# BK1096_USB.net
KiCad netlist of a schematic drawn in Altium Designer
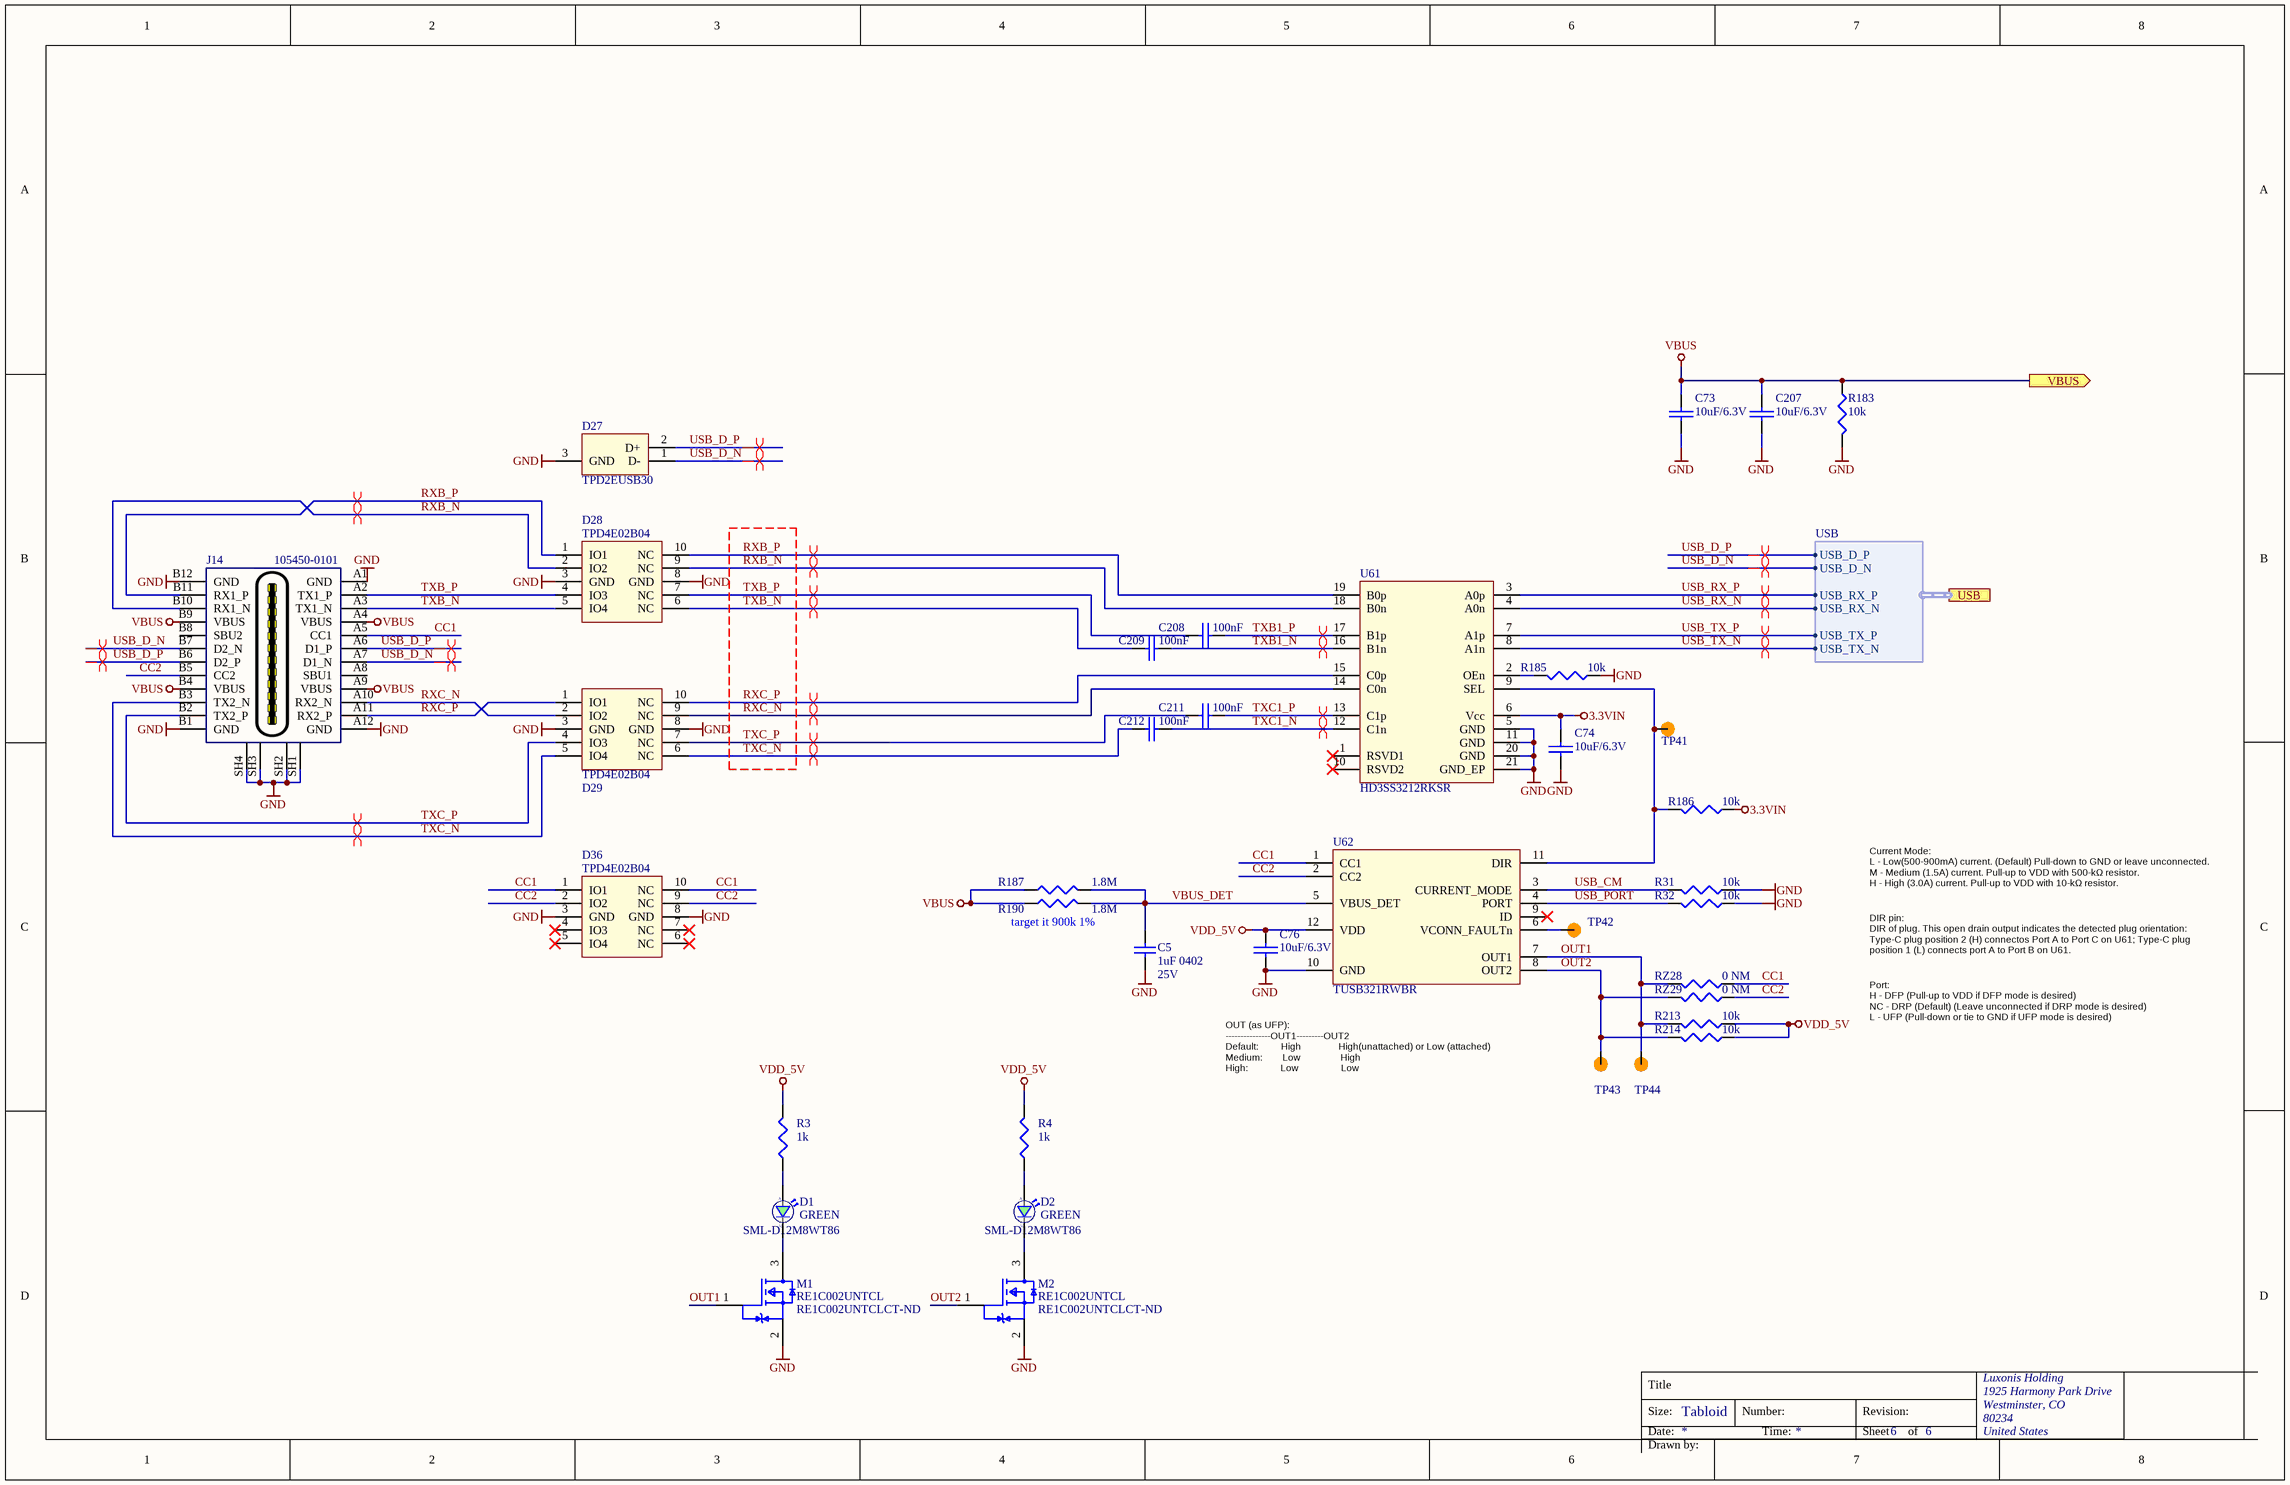
[diagram p0: BK1096_USB.SchDoc]

(export (version "E")
  (design (tool "Eeschema 10.0.6"))
  (components
    (comp (ref "C5")
      (value "1uF 0402")
      (footprint "CAP_Altium_Vault_Generic:CAPC0402(1005)70_N")
      (description "CAP CER 1UF 25V X5R 0402 10%")
      (fields
        (field (name "TOLERANCE") "10%")
        (field (name "VOLTAGE") "25V")
        (field (name "VOLTAGE RATING") "25V")
      )
      (libsource (lib "LuxonisMaster") (part "GRM155R61E105KA12D"))
    )
    (comp (ref "C73")
      (value "10uF/6.3V")
      (footprint "CAPC0402(1005)60_N")
      (description "SMD Multilayer Ceramic Capacitor, 0402 [1005 Metric], 10 µF, 6.3 V, ± 20%, X5R")
      (libsource (lib "*") (part "CAP"))
    )
    (comp (ref "C74")
      (value "10uF/6.3V")
      (footprint "CAPC0402(1005)60_N")
      (description "SMD Multilayer Ceramic Capacitor, 0402 [1005 Metric], 10 µF, 6.3 V, ± 20%, X5R")
      (libsource (lib "*") (part "CAP"))
    )
    (comp (ref "C76")
      (value "10uF/6.3V")
      (footprint "CAPC0402(1005)60_N")
      (description "SMD Multilayer Ceramic Capacitor, 0402 [1005 Metric], 10 µF, 6.3 V, ± 20%, X5R")
      (libsource (lib "*") (part "CAP"))
    )
    (comp (ref "C207")
      (value "10uF/6.3V")
      (footprint "CAPC0402(1005)60_N")
      (description "SMD Multilayer Ceramic Capacitor, 0402 [1005 Metric], 10 µF, 6.3 V, ± 20%, X5R")
      (libsource (lib "*") (part "CAP"))
    )
    (comp (ref "C208")
      (value "100nF")
      (footprint "CAPC0201(0603)33_L")
      (description "SMD Multilayer Ceramic Capacitor, 0201 [0603 Metric], 0.1 µF, 6.3 V, ± 10%, X5R")
      (libsource (lib "MV0235_R1M0E0") (part "CAP"))
    )
    (comp (ref "C209")
      (value "100nF")
      (footprint "CAPC0201(0603)33_L")
      (description "SMD Multilayer Ceramic Capacitor, 0201 [0603 Metric], 0.1 µF, 6.3 V, ± 10%, X5R")
      (libsource (lib "MV0235_R1M0E0") (part "CAP"))
    )
    (comp (ref "C211")
      (value "100nF")
      (footprint "CAPC0201(0603)33_L")
      (description "SMD Multilayer Ceramic Capacitor, 0201 [0603 Metric], 0.1 µF, 6.3 V, ± 10%, X5R")
      (libsource (lib "MV0235_R1M0E0") (part "CAP"))
    )
    (comp (ref "C212")
      (value "100nF")
      (footprint "CAPC0201(0603)33_L")
      (description "SMD Multilayer Ceramic Capacitor, 0201 [0603 Metric], 0.1 µF, 6.3 V, ± 10%, X5R")
      (libsource (lib "MV0235_R1M0E0") (part "CAP"))
    )
    (comp (ref "D1")
      (value "GREEN")
      (footprint "Luxonis:LED_0603")
      (description "LED GREEN DIFFUSED 0603 SMD")
      (fields (field (name "MANUFACTURER") "Rohm") (field (name "MANUFACTURER PART NUMBER") "SML-D12M8WT86"))
      (libsource (lib "Luxonis") (part "LED_GREEN_0603"))
    )
    (comp (ref "D2")
      (value "GREEN")
      (footprint "Luxonis:LED_0603")
      (description "LED GREEN DIFFUSED 0603 SMD")
      (fields (field (name "MANUFACTURER") "Rohm") (field (name "MANUFACTURER PART NUMBER") "SML-D12M8WT86"))
      (libsource (lib "Luxonis") (part "LED_GREEN_0603"))
    )
    (comp (ref "D27")
      (value "TPD2EUSB30")
      (footprint "Luxonis:SOT-3")
      (description "DIODE, ESD, DUAL, USB3.0, SOT-3")
      (libsource (lib "Myriad2") (part "TPD2EUSB30"))
    )
    (comp (ref "D28")
      (value "TPD4E02B04")
      (footprint "Luxonis:DQA-10")
      (description "TVS DIODE 3.6VWM 8.8VC 10USON")
      (libsource (lib "MV0248_R0M0E0") (part "TPD4E02B04"))
    )
    (comp (ref "D29")
      (value "TPD4E02B04")
      (footprint "Luxonis:DQA-10")
      (description "TVS DIODE 3.6VWM 8.8VC 10USON")
      (libsource (lib "MV0248_R0M0E0") (part "TPD4E02B04"))
    )
    (comp (ref "D36")
      (value "TPD4E02B04")
      (footprint "Luxonis:DQA-10")
      (description "TVS DIODE 3.6VWM 8.8VC 10USON")
      (libsource (lib "MV0248_R0M0E0") (part "TPD4E02B04"))
    )
    (comp (ref "J14")
      (value "105450-0101")
      (footprint "Luxonis:Molex_105450-0101")
      (description "USB 3.1 Type C Receptacle SMD RA")
      (libsource (lib "MyriadX_D") (part "Molex_1054500101"))
    )
    (comp (ref "M1")
      (value "RE1C002UNTCL")
      (footprint "Luxonis:SOT-416FL")
      (description "MOSFET N-CH 20V 0.2A EMT3")
      (fields (field (name "SUPPLIER PART NUMBER 1") "RE1C002UNTCLCT-ND"))
      (libsource (lib "Luxonis") (part "RE1C002UNTCL"))
    )
    (comp (ref "M2")
      (value "RE1C002UNTCL")
      (footprint "Luxonis:SOT-416FL")
      (description "MOSFET N-CH 20V 0.2A EMT3")
      (fields (field (name "SUPPLIER PART NUMBER 1") "RE1C002UNTCLCT-ND"))
      (libsource (lib "Luxonis") (part "RE1C002UNTCL"))
    )
    (comp (ref "R3")
      (value "1k")
      (footprint "IPC_RES_CAP:RESC0402(1005)_N")
      (description "SMD Chip Resistor, 1 kohm, 50 V, 0402 [1005 Metric], 62.5 mW, ± 1%")
      (libsource (lib "") (part "RES1_1"))
    )
    (comp (ref "R4")
      (value "1k")
      (footprint "IPC_RES_CAP:RESC0402(1005)_N")
      (description "SMD Chip Resistor, 1 kohm, 50 V, 0402 [1005 Metric], 62.5 mW, ± 1%")
      (libsource (lib "") (part "RES1_1"))
    )
    (comp (ref "R31")
      (value "10k")
      (footprint "RESC0402(1005)_N")
      (description "SMD Chip Resistor, Thick Film, 10 kohm, 50 V, 0402, 100mW, ± 1%")
      (libsource (lib "*") (part "RES1"))
    )
    (comp (ref "R32")
      (value "10k")
      (footprint "RESC0402(1005)_N")
      (description "SMD Chip Resistor, Thick Film, 10 kohm, 50 V, 0402, 100mW, ± 1%")
      (libsource (lib "*") (part "RES1"))
    )
    (comp (ref "R183")
      (value "10k")
      (footprint "RESC0402(1005)_N")
      (description "SMD Chip Resistor, Thick Film, 10 kohm, 50 V, 0402, 100mW, ± 1%")
      (libsource (lib "*") (part "RES1"))
    )
    (comp (ref "R185")
      (value "10k")
      (footprint "RESC0402(1005)_N")
      (description "SMD Chip Resistor, Thick Film, 10 kohm, 50 V, 0402, 100mW, ± 1%")
      (libsource (lib "*") (part "RES1"))
    )
    (comp (ref "R186")
      (value "10k")
      (footprint "RESC0402(1005)_N")
      (description "SMD Chip Resistor, Thick Film, 10 kohm, 50 V, 0402, 100mW, ± 1%")
      (libsource (lib "*") (part "RES1"))
    )
    (comp (ref "R187")
      (value "1.8M")
      (footprint "RESC0402(1005)_N")
      (description "RES SMD 1.8M 1% 0402 50V")
      (libsource (lib "MyriadX_D") (part "R_1.8M_1%_0402"))
    )
    (comp (ref "R190")
      (value "1.8M")
      (footprint "RESC0402(1005)_N")
      (description "RES SMD 1.8M 1% 0402 50V")
      (libsource (lib "MyriadX_D") (part "R_1.8M_1%_0402"))
    )
    (comp (ref "R213")
      (value "10k")
      (footprint "RESC0402(1005)_N")
      (description "SMD Chip Resistor, Thick Film, 10 kohm, 50 V, 0402, 100mW, ± 1%")
      (libsource (lib "*") (part "RES1"))
    )
    (comp (ref "R214")
      (value "10k")
      (footprint "RESC0402(1005)_N")
      (description "SMD Chip Resistor, Thick Film, 10 kohm, 50 V, 0402, 100mW, ± 1%")
      (libsource (lib "*") (part "RES1"))
    )
    (comp (ref "RZ28")
      (value "0 NM")
      (footprint "RESC0603(1608)_N")
      (description "Thick Film Resistors - SMD 0603 Zero Ohms")
      (libsource (lib "*") (part "RES1"))
    )
    (comp (ref "RZ29")
      (value "0 NM")
      (footprint "RESC0603(1608)_N")
      (description "Thick Film Resistors - SMD 0603 Zero Ohms")
      (libsource (lib "*") (part "RES1"))
    )
    (comp (ref "TP41")
      (value "TP_SMD")
      (footprint "TP_0.75MM_SMD_NO-SILK")
      (description "circular pad test point, SMD")
      (libsource (lib "Luxonis") (part "TP_SMD"))
    )
    (comp (ref "TP42")
      (value "TP_SMD")
      (footprint "TP_0.75MM_SMD_NO-SILK")
      (description "circular pad test point, SMD")
      (libsource (lib "Luxonis") (part "TP_SMD"))
    )
    (comp (ref "TP43")
      (value "TP_SMD")
      (footprint "TP_0.75MM_SMD_NO-SILK")
      (description "circular pad test point, SMD")
      (libsource (lib "Luxonis") (part "TP_SMD"))
    )
    (comp (ref "TP44")
      (value "TP_SMD")
      (footprint "TP_0.75MM_SMD_NO-SILK")
      (description "circular pad test point, SMD")
      (libsource (lib "Luxonis") (part "TP_SMD"))
    )
    (comp (ref "U61")
      (value "HD3SS3212RKSR")
      (footprint "Luxonis:VQFN-20")
      (description "Two Channel Differential 2:1/1:2 10Gbps Mux/Demux")
      (libsource (lib "MyriadX_D") (part "HD3SS3212RKSR"))
    )
    (comp (ref "U62")
      (value "TUSB321RWBR")
      (footprint "Luxonis:X2QFN-12")
      (description "USB Type-C  ™ Configuration  Channel  Logic and Port Control  with VCONN")
      (libsource (lib "MyriadX_D") (part "TUSB321RWBR"))
    )
  )
  (nets
    (net (code "2") (name "/CC1") (class "Default")
      (node (ref "D36") (pin "1") (pinfunction "IO1_1") (pintype "passive"))
      (node (ref "D36") (pin "10") (pinfunction "NC_10") (pintype "passive"))
      (node (ref "J14") (pin "A5") (pinfunction "CC1_A5") (pintype "passive"))
      (node (ref "RZ28") (pin "1") (pintype "passive"))
      (node (ref "U62") (pin "1") (pinfunction "CC1_1") (pintype "passive"))
    )
    (net (code "3") (name "/CC2") (class "Default")
      (node (ref "D36") (pin "2") (pinfunction "IO2_2") (pintype "passive"))
      (node (ref "D36") (pin "9") (pinfunction "NC_9") (pintype "passive"))
      (node (ref "J14") (pin "B5") (pinfunction "CC2_B5") (pintype "passive"))
      (node (ref "RZ29") (pin "1") (pintype "passive"))
      (node (ref "U62") (pin "2") (pinfunction "CC2_2") (pintype "passive"))
    )
    (net (code "4") (name "/OUT1") (class "Default")
      (node (ref "M1") (pin "1") (pinfunction "Gate_1") (pintype "passive"))
      (node (ref "R213") (pin "1") (pintype "passive"))
      (node (ref "RZ28") (pin "2") (pintype "passive"))
      (node (ref "TP44") (pin "1") (pintype "passive"))
      (node (ref "U62") (pin "7") (pinfunction "OUT1_7") (pintype "passive"))
    )
    (net (code "5") (name "/OUT2") (class "Default")
      (node (ref "M2") (pin "1") (pinfunction "Gate_1") (pintype "passive"))
      (node (ref "R214") (pin "1") (pintype "passive"))
      (node (ref "RZ29") (pin "2") (pintype "passive"))
      (node (ref "TP43") (pin "1") (pintype "passive"))
      (node (ref "U62") (pin "8") (pinfunction "OUT2_8") (pintype "passive"))
    )
    (net (code "6") (name "/RXB_N") (class "Default")
      (node (ref "D28") (pin "2") (pinfunction "IO2_2") (pintype "passive"))
      (node (ref "D28") (pin "9") (pinfunction "NC_9") (pintype "passive"))
      (node (ref "J14") (pin "B10") (pinfunction "RX1_N_B10") (pintype "passive"))
      (node (ref "U61") (pin "18") (pinfunction "B0n_18") (pintype "passive"))
    )
    (net (code "7") (name "/RXB_P") (class "Default")
      (node (ref "D28") (pin "1") (pinfunction "IO1_1") (pintype "passive"))
      (node (ref "D28") (pin "10") (pinfunction "NC_10") (pintype "passive"))
      (node (ref "J14") (pin "B11") (pinfunction "RX1_P_B11") (pintype "passive"))
      (node (ref "U61") (pin "19") (pinfunction "B0p_19") (pintype "passive"))
    )
    (net (code "8") (name "/RXC_N") (class "Default")
      (node (ref "D29") (pin "2") (pinfunction "IO2_2") (pintype "passive"))
      (node (ref "D29") (pin "9") (pinfunction "NC_9") (pintype "passive"))
      (node (ref "J14") (pin "A10") (pinfunction "RX2_N_A10") (pintype "passive"))
      (node (ref "U61") (pin "14") (pinfunction "C0n_14") (pintype "passive"))
    )
    (net (code "9") (name "/RXC_P") (class "Default")
      (node (ref "D29") (pin "1") (pinfunction "IO1_1") (pintype "passive"))
      (node (ref "D29") (pin "10") (pinfunction "NC_10") (pintype "passive"))
      (node (ref "J14") (pin "A11") (pinfunction "RX2_P_A11") (pintype "passive"))
      (node (ref "U61") (pin "15") (pinfunction "C0p_15") (pintype "passive"))
    )
    (net (code "10") (name "/TXB1_N") (class "Default")
      (node (ref "C209") (pin "1") (pinfunction "1_1") (pintype "passive"))
      (node (ref "U61") (pin "16") (pinfunction "B1n_16") (pintype "passive"))
    )
    (net (code "11") (name "/TXB1_P") (class "Default")
      (node (ref "C208") (pin "1") (pinfunction "1_1") (pintype "passive"))
      (node (ref "U61") (pin "17") (pinfunction "B1p_17") (pintype "passive"))
    )
    (net (code "12") (name "/TXB_N") (class "Default")
      (node (ref "C209") (pin "2") (pinfunction "2_2") (pintype "passive"))
      (node (ref "D28") (pin "5") (pinfunction "IO4_5") (pintype "passive"))
      (node (ref "D28") (pin "6") (pinfunction "NC_6") (pintype "passive"))
      (node (ref "J14") (pin "A3") (pinfunction "TX1_N_A3") (pintype "passive"))
    )
    (net (code "13") (name "/TXB_P") (class "Default")
      (node (ref "C208") (pin "2") (pinfunction "2_2") (pintype "passive"))
      (node (ref "D28") (pin "4") (pinfunction "IO3_4") (pintype "passive"))
      (node (ref "D28") (pin "7") (pinfunction "NC_7") (pintype "passive"))
      (node (ref "J14") (pin "A2") (pinfunction "TX1_P_A2") (pintype "passive"))
    )
    (net (code "14") (name "/TXC1_N") (class "Default")
      (node (ref "C212") (pin "1") (pinfunction "1_1") (pintype "passive"))
      (node (ref "U61") (pin "12") (pinfunction "C1n_12") (pintype "passive"))
    )
    (net (code "15") (name "/TXC1_P") (class "Default")
      (node (ref "C211") (pin "1") (pinfunction "1_1") (pintype "passive"))
      (node (ref "U61") (pin "13") (pinfunction "C1p_13") (pintype "passive"))
    )
    (net (code "16") (name "/TXC_N") (class "Default")
      (node (ref "C212") (pin "2") (pinfunction "2_2") (pintype "passive"))
      (node (ref "D29") (pin "5") (pinfunction "IO4_5") (pintype "passive"))
      (node (ref "D29") (pin "6") (pinfunction "NC_6") (pintype "passive"))
      (node (ref "J14") (pin "B3") (pinfunction "TX2_N_B3") (pintype "passive"))
    )
    (net (code "17") (name "/TXC_P") (class "Default")
      (node (ref "C211") (pin "2") (pinfunction "2_2") (pintype "passive"))
      (node (ref "D29") (pin "4") (pinfunction "IO3_4") (pintype "passive"))
      (node (ref "D29") (pin "7") (pinfunction "NC_7") (pintype "passive"))
      (node (ref "J14") (pin "B2") (pinfunction "TX2_P_B2") (pintype "passive"))
    )
    (net (code "18") (name "/USB_CM") (class "Default")
      (node (ref "R31") (pin "1") (pintype "passive"))
      (node (ref "U62") (pin "3") (pinfunction "CURRENT_MODE_3") (pintype "passive"))
    )
    (net (code "19") (name "/USB_D_N") (class "Default")
      (node (ref "D27") (pin "1") (pinfunction "D-_1") (pintype "passive"))
      (node (ref "J14") (pin "A7") (pinfunction "D1_N_A7") (pintype "passive"))
      (node (ref "J14") (pin "B7") (pinfunction "D2_N_B7") (pintype "passive"))
    )
    (net (code "20") (name "/USB_D_P") (class "Default")
      (node (ref "D27") (pin "2") (pinfunction "D+_2") (pintype "passive"))
      (node (ref "J14") (pin "A6") (pinfunction "D1_P_A6") (pintype "passive"))
      (node (ref "J14") (pin "B6") (pinfunction "D2_P_B6") (pintype "passive"))
    )
    (net (code "21") (name "/USB_PORT") (class "Default")
      (node (ref "R32") (pin "1") (pintype "passive"))
      (node (ref "U62") (pin "4") (pinfunction "PORT_4") (pintype "passive"))
    )
    (net (code "22") (name "/USB_RX_N") (class "Default")
      (node (ref "U61") (pin "4") (pinfunction "A0n_4") (pintype "passive"))
    )
    (net (code "23") (name "/USB_RX_P") (class "Default")
      (node (ref "U61") (pin "3") (pinfunction "A0p_3") (pintype "passive"))
    )
    (net (code "24") (name "/USB_TX_N") (class "Default")
      (node (ref "U61") (pin "8") (pinfunction "A1n_8") (pintype "passive"))
    )
    (net (code "25") (name "/USB_TX_P") (class "Default")
      (node (ref "U61") (pin "7") (pinfunction "A1p_7") (pintype "passive"))
    )
    (net (code "26") (name "/VBUS_DET") (class "Default")
      (node (ref "C5") (pin "2") (pinfunction "2_2") (pintype "passive"))
      (node (ref "R187") (pin "1") (pintype "passive"))
      (node (ref "R190") (pin "1") (pintype "passive"))
      (node (ref "U62") (pin "5") (pinfunction "VBUS_DET_5") (pintype "passive"))
    )
    (net (code "28") (name "3.3VIN") (class "Default")
      (node (ref "C74") (pin "2") (pinfunction "2_2") (pintype "passive"))
      (node (ref "R186") (pin "2") (pintype "passive"))
      (node (ref "U61") (pin "6") (pinfunction "Vcc_6") (pintype "passive"))
    )
    (net (code "29") (name "GND") (class "Default")
      (node (ref "C207") (pin "1") (pinfunction "1_1") (pintype "passive"))
      (node (ref "C5") (pin "1") (pinfunction "1_1") (pintype "passive"))
      (node (ref "C73") (pin "1") (pinfunction "1_1") (pintype "passive"))
      (node (ref "C74") (pin "1") (pinfunction "1_1") (pintype "passive"))
      (node (ref "C76") (pin "1") (pinfunction "1_1") (pintype "passive"))
      (node (ref "D27") (pin "3") (pinfunction "GND_3") (pintype "passive"))
      (node (ref "D28") (pin "3") (pinfunction "GND_3") (pintype "passive"))
      (node (ref "D28") (pin "8") (pinfunction "GND_8") (pintype "passive"))
      (node (ref "D29") (pin "3") (pinfunction "GND_3") (pintype "passive"))
      (node (ref "D29") (pin "8") (pinfunction "GND_8") (pintype "passive"))
      (node (ref "D36") (pin "3") (pinfunction "GND_3") (pintype "passive"))
      (node (ref "D36") (pin "8") (pinfunction "GND_8") (pintype "passive"))
      (node (ref "J14") (pin "A1") (pinfunction "GND_A1") (pintype "passive"))
      (node (ref "J14") (pin "A12") (pinfunction "GND_A12") (pintype "passive"))
      (node (ref "J14") (pin "B1") (pinfunction "GND_B1") (pintype "passive"))
      (node (ref "J14") (pin "B12") (pinfunction "GND_B12") (pintype "passive"))
      (node (ref "J14") (pin "SH1") (pinfunction "SH_SH1") (pintype "passive"))
      (node (ref "J14") (pin "SH2") (pinfunction "SH_SH2") (pintype "passive"))
      (node (ref "J14") (pin "SH3") (pinfunction "SH_SH3") (pintype "passive"))
      (node (ref "J14") (pin "SH4") (pinfunction "SH_SH4") (pintype "passive"))
      (node (ref "M1") (pin "2") (pinfunction "Source_2") (pintype "passive"))
      (node (ref "M2") (pin "2") (pinfunction "Source_2") (pintype "passive"))
      (node (ref "R183") (pin "1") (pintype "passive"))
      (node (ref "R185") (pin "2") (pintype "passive"))
      (node (ref "R31") (pin "2") (pintype "passive"))
      (node (ref "R32") (pin "2") (pintype "passive"))
      (node (ref "U61") (pin "11") (pinfunction "GND_11") (pintype "passive"))
      (node (ref "U61") (pin "20") (pinfunction "GND_20") (pintype "passive"))
      (node (ref "U61") (pin "21") (pinfunction "GND_EP_21") (pintype "passive"))
      (node (ref "U61") (pin "5") (pinfunction "GND_5") (pintype "passive"))
      (node (ref "U62") (pin "10") (pinfunction "GND_10") (pintype "passive"))
    )
    (net (code "30") (name "Net-(D1-A)") (class "Default")
      (node (ref "D1") (pin "2") (pinfunction "A_2") (pintype "passive"))
      (node (ref "R3") (pin "1") (pintype "passive"))
    )
    (net (code "31") (name "Net-(D1-C)") (class "Default")
      (node (ref "D1") (pin "1") (pinfunction "C_1") (pintype "passive"))
      (node (ref "M1") (pin "3") (pinfunction "Drain_3") (pintype "passive"))
    )
    (net (code "32") (name "Net-(D2-A)") (class "Default")
      (node (ref "D2") (pin "2") (pinfunction "A_2") (pintype "passive"))
      (node (ref "R4") (pin "1") (pintype "passive"))
    )
    (net (code "33") (name "Net-(D2-C)") (class "Default")
      (node (ref "D2") (pin "1") (pinfunction "C_1") (pintype "passive"))
      (node (ref "M2") (pin "3") (pinfunction "Drain_3") (pintype "passive"))
    )
    (net (code "34") (name "Net-(U61-OEn)") (class "Default")
      (node (ref "R185") (pin "1") (pintype "passive"))
      (node (ref "U61") (pin "2") (pinfunction "OEn_2") (pintype "passive"))
    )
    (net (code "35") (name "Net-(U61-SEL)") (class "Default")
      (node (ref "R186") (pin "1") (pintype "passive"))
      (node (ref "TP41") (pin "1") (pintype "passive"))
      (node (ref "U61") (pin "9") (pinfunction "SEL_9") (pintype "passive"))
      (node (ref "U62") (pin "11") (pinfunction "DIR_11") (pintype "passive"))
    )
    (net (code "36") (name "Net-(U62-VCONN_FAULTn)") (class "Default")
      (node (ref "TP42") (pin "1") (pintype "passive"))
      (node (ref "U62") (pin "6") (pinfunction "VCONN_FAULTn_6") (pintype "passive"))
    )
    (net (code "37") (name "VBUS") (class "Default")
      (node (ref "C207") (pin "2") (pinfunction "2_2") (pintype "passive"))
      (node (ref "C73") (pin "2") (pinfunction "2_2") (pintype "passive"))
      (node (ref "J14") (pin "A4") (pinfunction "VBUS_A4") (pintype "passive"))
      (node (ref "J14") (pin "A9") (pinfunction "VBUS_A9") (pintype "passive"))
      (node (ref "J14") (pin "B4") (pinfunction "VBUS_B4") (pintype "passive"))
      (node (ref "J14") (pin "B9") (pinfunction "VBUS_B9") (pintype "passive"))
      (node (ref "R183") (pin "2") (pintype "passive"))
      (node (ref "R187") (pin "2") (pintype "passive"))
      (node (ref "R190") (pin "2") (pintype "passive"))
    )
    (net (code "38") (name "VDD_5V") (class "Default")
      (node (ref "C76") (pin "2") (pinfunction "2_2") (pintype "passive"))
      (node (ref "R213") (pin "2") (pintype "passive"))
      (node (ref "R214") (pin "2") (pintype "passive"))
      (node (ref "R3") (pin "2") (pintype "passive"))
      (node (ref "R4") (pin "2") (pintype "passive"))
      (node (ref "U62") (pin "12") (pinfunction "VDD_12") (pintype "passive"))
    )
    (net (code "39") (name "unconnected-(D36-IO3-Pad4)") (class "Default")
      (node (ref "D36") (pin "4") (pinfunction "IO3_4") (pintype "passive+no_connect"))
    )
    (net (code "40") (name "unconnected-(D36-IO4-Pad5)") (class "Default")
      (node (ref "D36") (pin "5") (pinfunction "IO4_5") (pintype "passive+no_connect"))
    )
    (net (code "41") (name "unconnected-(D36-NC-Pad6)") (class "Default")
      (node (ref "D36") (pin "6") (pinfunction "NC_6") (pintype "passive+no_connect"))
    )
    (net (code "42") (name "unconnected-(D36-NC-Pad7)") (class "Default")
      (node (ref "D36") (pin "7") (pinfunction "NC_7") (pintype "passive+no_connect"))
    )
    (net (code "43") (name "unconnected-(J14-SBU1-PadA8)") (class "Default")
      (node (ref "J14") (pin "A8") (pinfunction "SBU1_A8") (pintype "passive"))
    )
    (net (code "44") (name "unconnected-(J14-SBU2-PadB8)") (class "Default")
      (node (ref "J14") (pin "B8") (pinfunction "SBU2_B8") (pintype "passive"))
    )
    (net (code "45") (name "unconnected-(U61-RSVD1-Pad1)") (class "Default")
      (node (ref "U61") (pin "1") (pinfunction "RSVD1_1") (pintype "passive+no_connect"))
    )
    (net (code "46") (name "unconnected-(U61-RSVD2-Pad10)") (class "Default")
      (node (ref "U61") (pin "10") (pinfunction "RSVD2_10") (pintype "passive+no_connect"))
    )
    (net (code "47") (name "unconnected-(U62-ID-Pad9)") (class "Default")
      (node (ref "U62") (pin "9") (pinfunction "ID_9") (pintype "passive+no_connect"))
    )
  )
)
